# SH3_-_24V_BUCK-BOOST_CONVERTER.net
KiCad netlist of a schematic drawn in Altium Designer
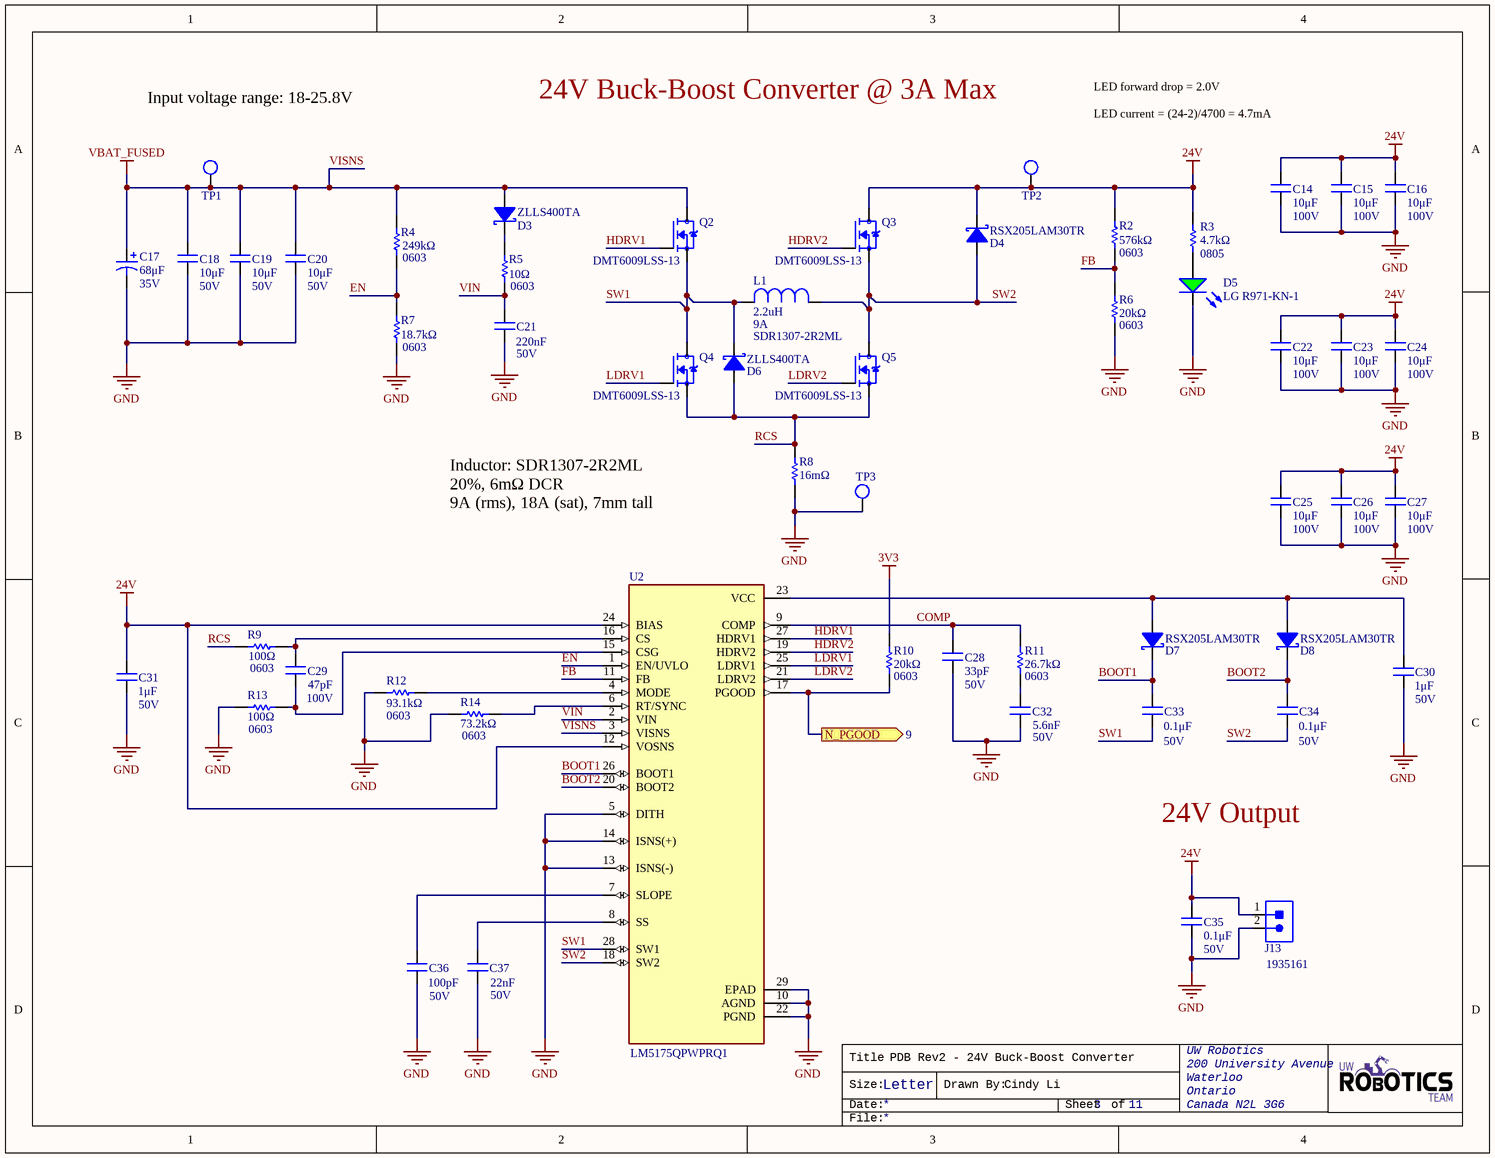
[diagram p0: SH3 - 24V BUCK-BOOST CONVERTER.SchDoc]

(export (version "E")
  (design (tool "Eeschema 10.0.6"))
  (components
    (comp (ref "C14")
      (value "10μF")
      (footprint "CAP1210")
      (description "CAP CER 10uF 100V X7S 10% 1210")
      (fields
        (field (name "TOLERANCE") "10%")
        (field (name "VOLTAGE RATING") "100V")
        (field (name "Comment") "CAP_10uF_100V_1210")
      )
      (libsource (lib "UWRT_Schematic_Library_2020") (part "CAP_10uF_100V_1210"))
    )
    (comp (ref "C15")
      (value "10μF")
      (footprint "CAP1210")
      (description "CAP CER 10uF 100V X7S 10% 1210")
      (fields
        (field (name "TOLERANCE") "10%")
        (field (name "VOLTAGE RATING") "100V")
        (field (name "Comment") "CAP_10uF_100V_1210")
      )
      (libsource (lib "UWRT_Schematic_Library_2020") (part "CAP_10uF_100V_1210"))
    )
    (comp (ref "C16")
      (value "10μF")
      (footprint "CAP1210")
      (description "CAP CER 10uF 100V X7S 10% 1210")
      (fields
        (field (name "TOLERANCE") "10%")
        (field (name "VOLTAGE RATING") "100V")
        (field (name "Comment") "CAP_10uF_100V_1210")
      )
      (libsource (lib "UWRT_Schematic_Library_2020") (part "CAP_10uF_100V_1210"))
    )
    (comp (ref "C17")
      (value "68μF")
      (footprint "RADIAL_NICHION_1V")
      (description "CAP ALUM 68UF 20% 35V SMD")
      (fields
        (field (name "TOLERANCE") "20%")
        (field (name "VOLTAGE RATING") "35V")
        (field (name "Comment") "CAP_68uF_35V_ALUM")
      )
      (libsource (lib "UWRT_Schematic_Library_2020") (part "CAP_68uF_35V_ALUM"))
    )
    (comp (ref "C18")
      (value "10μF")
      (footprint "CAP1210")
      (description "CAP CER 10UF 50V X7R 1210")
      (fields
        (field (name "TOLERANCE") "20%")
        (field (name "VOLTAGE RATING") "50V")
        (field (name "Comment") "CAP_10uF_50V_1210_TDK")
      )
      (libsource (lib "UWRT_Schematic_Library_2020") (part "CAP_10uF_50V_1210_TDK"))
    )
    (comp (ref "C19")
      (value "10μF")
      (footprint "CAP1210")
      (description "CAP CER 10UF 50V X7R 1210")
      (fields
        (field (name "TOLERANCE") "20%")
        (field (name "VOLTAGE RATING") "50V")
        (field (name "Comment") "CAP_10uF_50V_1210_TDK")
      )
      (libsource (lib "UWRT_Schematic_Library_2020") (part "CAP_10uF_50V_1210_TDK"))
    )
    (comp (ref "C20")
      (value "10μF")
      (footprint "CAP1210")
      (description "CAP CER 10UF 50V X7R 1210")
      (fields
        (field (name "TOLERANCE") "20%")
        (field (name "VOLTAGE RATING") "50V")
        (field (name "Comment") "CAP_10uF_50V_1210_TDK")
      )
      (libsource (lib "UWRT_Schematic_Library_2020") (part "CAP_10uF_50V_1210_TDK"))
    )
    (comp (ref "C21")
      (value "220nF")
      (footprint "CAP0603")
      (description "CAP CER 0.22UF 50V X7R 0603")
      (fields (field (name "VOLTAGE RATING") "50V") (field (name "Comment") "CAP_0.22uF_50V_0603"))
      (libsource (lib "UWRT_Schematic_Library_2020") (part "CAP_0.22uF_50V_0603"))
    )
    (comp (ref "C22")
      (value "10μF")
      (footprint "CAP1210")
      (description "CAP CER 10uF 100V X7S 10% 1210")
      (fields
        (field (name "TOLERANCE") "10%")
        (field (name "VOLTAGE RATING") "100V")
        (field (name "Comment") "CAP_10uF_100V_1210")
      )
      (libsource (lib "UWRT_Schematic_Library_2020") (part "CAP_10uF_100V_1210"))
    )
    (comp (ref "C23")
      (value "10μF")
      (footprint "CAP1210")
      (description "CAP CER 10uF 100V X7S 10% 1210")
      (fields
        (field (name "TOLERANCE") "10%")
        (field (name "VOLTAGE RATING") "100V")
        (field (name "Comment") "CAP_10uF_100V_1210")
      )
      (libsource (lib "UWRT_Schematic_Library_2020") (part "CAP_10uF_100V_1210"))
    )
    (comp (ref "C24")
      (value "10μF")
      (footprint "CAP1210")
      (description "CAP CER 10uF 100V X7S 10% 1210")
      (fields
        (field (name "TOLERANCE") "10%")
        (field (name "VOLTAGE RATING") "100V")
        (field (name "Comment") "CAP_10uF_100V_1210")
      )
      (libsource (lib "UWRT_Schematic_Library_2020") (part "CAP_10uF_100V_1210"))
    )
    (comp (ref "C25")
      (value "10μF")
      (footprint "CAP1210")
      (description "CAP CER 10uF 100V X7S 10% 1210")
      (fields
        (field (name "TOLERANCE") "10%")
        (field (name "VOLTAGE RATING") "100V")
        (field (name "Comment") "CAP_10uF_100V_1210")
      )
      (libsource (lib "UWRT_Schematic_Library_2020") (part "CAP_10uF_100V_1210"))
    )
    (comp (ref "C26")
      (value "10μF")
      (footprint "CAP1210")
      (description "CAP CER 10uF 100V X7S 10% 1210")
      (fields
        (field (name "TOLERANCE") "10%")
        (field (name "VOLTAGE RATING") "100V")
        (field (name "Comment") "CAP_10uF_100V_1210")
      )
      (libsource (lib "UWRT_Schematic_Library_2020") (part "CAP_10uF_100V_1210"))
    )
    (comp (ref "C27")
      (value "10μF")
      (footprint "CAP1210")
      (description "CAP CER 10uF 100V X7S 10% 1210")
      (fields
        (field (name "TOLERANCE") "10%")
        (field (name "VOLTAGE RATING") "100V")
        (field (name "Comment") "CAP_10uF_100V_1210")
      )
      (libsource (lib "UWRT_Schematic_Library_2020") (part "CAP_10uF_100V_1210"))
    )
    (comp (ref "C28")
      (value "33pF")
      (footprint "CAP2012")
      (description "CAP CER 33PF 50V C0G/NP0 0805")
      (fields
        (field (name "TOLERANCE") "5%")
        (field (name "VOLTAGE RATING") "50V")
        (field (name "Comment") "CAP_33pF_50V_0805")
      )
      (libsource (lib "UWRT_Schematic_Library_2020") (part "CAP_33pF_50V_0805"))
    )
    (comp (ref "C29")
      (value "47pF")
      (footprint "CAP0603")
      (description "CAP CER 47PF 100V C0G/NP0 0603")
      (fields (field (name "VOLTAGE RATING") "100V") (field (name "Comment") "CAP_47pF_100V_0603"))
      (libsource (lib "UWRT_Schematic_Library_2020") (part "CAP_47pF_100V_0603"))
    )
    (comp (ref "C30")
      (value "1μF")
      (footprint "CAP0603")
      (description "CAP CER 1UF 50V X6S 0603")
      (fields (field (name "VOLTAGE RATING") "50V") (field (name "Comment") "CAP_1uF_50V_0603"))
      (libsource (lib "UWRT_Schematic_Library_2020") (part "CAP_1uF_50V_0603"))
    )
    (comp (ref "C31")
      (value "1μF")
      (footprint "CAP0603")
      (description "CAP CER 1UF 50V X6S 0603")
      (fields (field (name "VOLTAGE RATING") "50V") (field (name "Comment") "CAP_1uF_50V_0603"))
      (libsource (lib "UWRT_Schematic_Library_2020") (part "CAP_1uF_50V_0603"))
    )
    (comp (ref "C32")
      (value "5600pF")
      (footprint "CAP2012")
      (description "CAP CER 5600PF 50V C0G 0805")
      (fields
        (field (name "TOLERANCE") "5%")
        (field (name "CAPACITANCE") "5.6nF")
        (field (name "VOLTAGE RATING") "50V")
      )
      (libsource (lib "UWRT_Schematic_Library_2020") (part "CAP_5600pF_50V_0805"))
    )
    (comp (ref "C33")
      (value "0.1μF")
      (footprint "CAP2012")
      (description "CAP CER 0.1UF 50V X7R 0805")
      (fields (field (name "TOLERANCE") "10%") (field (name "VOLTAGE RATING") "50V"))
      (libsource (lib "UWRT_Schematic_Library_2020") (part "CAP_0.1uF_50V_0805"))
    )
    (comp (ref "C34")
      (value "0.1μF")
      (footprint "CAP2012")
      (description "CAP CER 0.1UF 50V X7R 0805")
      (fields (field (name "TOLERANCE") "10%") (field (name "VOLTAGE RATING") "50V"))
      (libsource (lib "UWRT_Schematic_Library_2020") (part "CAP_0.1uF_50V_0805"))
    )
    (comp (ref "C35")
      (value "0.1μF")
      (footprint "CAP2012")
      (description "CAP CER 0.1UF 50V X7R 0805")
      (fields (field (name "TOLERANCE") "10%") (field (name "VOLTAGE RATING") "50V"))
      (libsource (lib "UWRT_Schematic_Library_2020") (part "CAP_0.1uF_50V_0805"))
    )
    (comp (ref "C36")
      (value "100pF")
      (footprint "CAP0603")
      (description "CAP CER 100PF 50V C0G/NP0 0603")
      (fields (field (name "VOLTAGE RATING") "50V") (field (name "Comment") "CAP_100pF_0603"))
      (libsource (lib "UWRT_Schematic_Library_2020") (part "CAP_100pF_0603"))
    )
    (comp (ref "C37")
      (value "22nF")
      (footprint "CAP2012")
      (description "CAP CER 0.022UF 50V C0G 0805")
      (fields
        (field (name "TOLERANCE") "5%")
        (field (name "VOLTAGE RATING") "50V")
        (field (name "Comment") "0.022μF")
      )
      (libsource (lib "UWRT_Schematic_Library_2020") (part "CAP_0.022uF_50V_0805"))
    )
    (comp (ref "D3")
      (value "DIO_SCHOTTKY_40V_520mA")
      (footprint "SOD-323")
      (description "DIODE SCHOTTKY 40V 520MA SOD323")
      (fields (field (name "MANUFACTURER PART NUMBER 1") "ZLLS400TA"))
      (libsource (lib "UWRT_Schematic_Library_2020") (part "DIO_SCHOTTKY_40V_520mA"))
    )
    (comp (ref "D4")
      (value "DIO_SCHOTTKY_30V_2A")
      (footprint "SOD-128")
      (description "DIODE SCHOTTKY 30V 2A PMDTM")
      (fields (field (name "MANUFACTURER PART NUMBER 1") "RSX205LAM30TR"))
      (libsource (lib "UWRT_Schematic_Library_2020") (part "DIO_SCHOTTKY_30V_2A"))
    )
    (comp (ref "D5")
      (value "LG R971-KN-1")
      (footprint "LED_0805_GREEN")
      (description "LED GREEN DIFFUSED 0805 SMD")
      (libsource (lib "UWRT_Schematic_Library_2020") (part "DIO_LED_G"))
    )
    (comp (ref "D6")
      (value "DIO_SCHOTTKY_40V_520mA")
      (footprint "SOD-323")
      (description "DIODE SCHOTTKY 40V 520MA SOD323")
      (fields (field (name "MANUFACTURER PART NUMBER 1") "ZLLS400TA"))
      (libsource (lib "UWRT_Schematic_Library_2020") (part "DIO_SCHOTTKY_40V_520mA"))
    )
    (comp (ref "D7")
      (value "DIO_SCHOTTKY_30V_2A")
      (footprint "SOD-128")
      (description "DIODE SCHOTTKY 30V 2A PMDTM")
      (fields (field (name "MANUFACTURER PART NUMBER 1") "RSX205LAM30TR"))
      (libsource (lib "UWRT_Schematic_Library_2020") (part "DIO_SCHOTTKY_30V_2A"))
    )
    (comp (ref "D8")
      (value "DIO_SCHOTTKY_30V_2A")
      (footprint "SOD-128")
      (description "DIODE SCHOTTKY 30V 2A PMDTM")
      (fields (field (name "MANUFACTURER PART NUMBER 1") "RSX205LAM30TR"))
      (libsource (lib "UWRT_Schematic_Library_2020") (part "DIO_SCHOTTKY_30V_2A"))
    )
    (comp (ref "J13")
      (value "1935161")
      (footprint "1935161")
      (description "TERM BLK 2POS SIDE ENTRY 5MM")
      (fields (field (name "VOLTAGE") "300V") (field (name "MANUFACTURER PART NUMBER 1") "1935161"))
      (libsource (lib "UWRT_Schematic_Library_2020") (part "CON_2M_TERM"))
    )
    (comp (ref "L1")
      (value "IND_2.2uH_9A")
      (footprint "IND_BOURNS_SDR1307")
      (description "FIXED IND 2.2UH 9A 6 MOHM SMD")
      (fields
        (field (name "TOLERANCE") "20%")
        (field (name "CURRENT RATING") "9A")
        (field (name "MANUFACTURER PART NUMBER 1") "SDR1307-2R2ML")
        (field (name "INDUCTANCE") "2.2uH")
      )
      (libsource (lib "UWRT_Schematic_Library_2020") (part "IND_2.2uH_9A"))
    )
    (comp (ref "Q2")
      (value "NMOS_60V_10.8A")
      (footprint "TRANS_DMP2002UPS-13")
      (description "MOSFET BVDSS: 41V 60V,SO-8,T&R,2")
      (fields (field (name "MANUFACTURER PART NUMBER 1") "DMT6009LSS-13"))
      (libsource (lib "UWRT_Schematic_Library_2020") (part "NMOS_60V_10.8A"))
    )
    (comp (ref "Q3")
      (value "NMOS_60V_10.8A")
      (footprint "TRANS_DMP2002UPS-13")
      (description "MOSFET BVDSS: 41V 60V,SO-8,T&R,2")
      (fields (field (name "MANUFACTURER PART NUMBER 1") "DMT6009LSS-13"))
      (libsource (lib "UWRT_Schematic_Library_2020") (part "NMOS_60V_10.8A"))
    )
    (comp (ref "Q4")
      (value "NMOS_60V_10.8A")
      (footprint "TRANS_DMP2002UPS-13")
      (description "MOSFET BVDSS: 41V 60V,SO-8,T&R,2")
      (fields (field (name "MANUFACTURER PART NUMBER 1") "DMT6009LSS-13"))
      (libsource (lib "UWRT_Schematic_Library_2020") (part "NMOS_60V_10.8A"))
    )
    (comp (ref "Q5")
      (value "NMOS_60V_10.8A")
      (footprint "TRANS_DMP2002UPS-13")
      (description "MOSFET BVDSS: 41V 60V,SO-8,T&R,2")
      (fields (field (name "MANUFACTURER PART NUMBER 1") "DMT6009LSS-13"))
      (libsource (lib "UWRT_Schematic_Library_2020") (part "NMOS_60V_10.8A"))
    )
    (comp (ref "R2")
      (value "576kΩ")
      (footprint "RESC0603(1608)_N")
      (description "RES 576K OHM 1% 1/10W 0603")
      (fields
        (field (name "CASE CODE (IMPERIAL)") "0603")
        (field (name "TOLERANCE") "1%")
        (field (name "Comment") "RES_576kΩ_0603")
      )
      (libsource (lib "UWRT_Schematic_Library_2020") (part "RES_576kΩ_0603_1%"))
    )
    (comp (ref "R3")
      (value "4.7kΩ")
      (footprint "RESC2012X60N")
      (description "RES 4.7K OHM 5% 1/8W 0805")
      (fields
        (field (name "TOLERANCE") "5%")
        (field (name "CASE CODE (IMPERIAL)") "0805")
        (field (name "Comment") "RES_4.7kΩ_0805")
      )
      (libsource (lib "UWRT_Schematic_Library_2020") (part "RES_4.7kΩ_0805_5%"))
    )
    (comp (ref "R4")
      (value "249kΩ")
      (footprint "RESC0603(1608)_N")
      (description "RES 249K OHM 1% 1/10W 0603")
      (fields
        (field (name "CASE CODE (IMPERIAL)") "0603")
        (field (name "POWER") "0.1W")
        (field (name "TOLERANCE") "1%")
      )
      (libsource (lib "UWRT_Schematic_Library_2020") (part "RES_249kΩ_0603_1%"))
    )
    (comp (ref "R5")
      (value "10Ω")
      (footprint "RESC0603(1608)_N")
      (description "RES 10 OHM 1% 1/10W 0603")
      (fields
        (field (name "CASE CODE (IMPERIAL)") "0603")
        (field (name "TOLERANCE") "1%")
        (field (name "Comment") "RES_10Ω_0603")
      )
      (libsource (lib "UWRT_Schematic_Library_2020") (part "RES_10Ω_0603_1%"))
    )
    (comp (ref "R6")
      (value "20kΩ")
      (footprint "RESC0603(1608)_N")
      (description "RES 20K OHM 1% 1/10W 0603")
      (fields
        (field (name "CASE CODE (IMPERIAL)") "0603")
        (field (name "TOLERANCE") "1%")
        (field (name "Comment") "RES_20kΩ_0603")
      )
      (libsource (lib "UWRT_Schematic_Library_2020") (part "RES_20kΩ_0603_1%"))
    )
    (comp (ref "R7")
      (value "18.7kΩ")
      (footprint "RESC0603(1608)_N")
      (description "RES 18.7K OHM 1% 1/10W 0603")
      (fields
        (field (name "CASE CODE (IMPERIAL)") "0603")
        (field (name "TOLERANCE") "1%")
        (field (name "Comment") "RES_18.7kΩ_0603_1%")
      )
      (libsource (lib "UWRT_Schematic_Library_2020") (part "RES_18.7kΩ_0603_1%"))
    )
    (comp (ref "R8")
      (value "16mΩ")
      (footprint "RESC1632X60N")
      (description "RES 0.016 OHM 1W 1206 WIDE")
      (fields (field (name "TOLERANCE") "1%") (field (name "Comment") "RES_16mΩ_1206"))
      (libsource (lib "UWRT_Schematic_Library_2020") (part "RES_16mΩ_1206_1%"))
    )
    (comp (ref "R9")
      (value "100Ω")
      (footprint "RESC0603(1608)_N")
      (description "RES 100 OHM 1% 1/10W 0603")
      (fields
        (field (name "CASE CODE (IMPERIAL)") "0603")
        (field (name "TOLERANCE") "1%")
        (field (name "Comment") "RES_100Ω_0603")
      )
      (libsource (lib "UWRT_Schematic_Library_2020") (part "RES_100Ω_0603_1%"))
    )
    (comp (ref "R10")
      (value "20kΩ")
      (footprint "RESC0603(1608)_N")
      (description "RES 20K OHM 1% 1/10W 0603")
      (fields
        (field (name "CASE CODE (IMPERIAL)") "0603")
        (field (name "TOLERANCE") "1%")
        (field (name "Comment") "RES_20kΩ_0603")
      )
      (libsource (lib "UWRT_Schematic_Library_2020") (part "RES_20kΩ_0603_1%"))
    )
    (comp (ref "R11")
      (value "26.7kΩ")
      (footprint "RESC0603(1608)_N")
      (description "RES 26.7K OHM 1% 1/10W 0603")
      (fields
        (field (name "CASE CODE (IMPERIAL)") "0603")
        (field (name "POWER") "0.1W")
        (field (name "TOLERANCE") "1%")
      )
      (libsource (lib "UWRT_Schematic_Library_2020") (part "RES_26.7kΩ_0603_1%"))
    )
    (comp (ref "R12")
      (value "93.1kΩ")
      (footprint "RESC0603(1608)_N")
      (description "RES 93.1K OHM 1% 1/10W 0603")
      (fields
        (field (name "TOLERANCE") "1%")
        (field (name "CASE CODE (IMPERIAL)") "0603")
        (field (name "Comment") "RES_93.1kΩ_0603")
      )
      (libsource (lib "UWRT_Schematic_Library_2020") (part "RES_93.1kΩ_0603_1%"))
    )
    (comp (ref "R13")
      (value "100Ω")
      (footprint "RESC0603(1608)_N")
      (description "RES 100 OHM 1% 1/10W 0603")
      (fields
        (field (name "CASE CODE (IMPERIAL)") "0603")
        (field (name "TOLERANCE") "1%")
        (field (name "Comment") "RES_100Ω_0603")
      )
      (libsource (lib "UWRT_Schematic_Library_2020") (part "RES_100Ω_0603_1%"))
    )
    (comp (ref "R14")
      (value "73.2kΩ")
      (footprint "RESC0603(1608)_N")
      (description "RES 73.2K OHM 1% 1/16W 0603")
      (fields
        (field (name "CASE CODE (IMPERIAL)") "0603")
        (field (name "TOLERANCE") "1%")
        (field (name "Comment") "RES_73.2kΩ_0603")
      )
      (libsource (lib "UWRT_Schematic_Library_2020") (part "RES_73.2kΩ_0603_1%"))
    )
    (comp (ref "TP1")
      (value "TESTPOINT_LOOP")
      (footprint "TESTPOINT_LOOP")
      (description "PC TEST POINT MINIATURE WHITE")
      (libsource (lib "UWRT_Schematic_Library_2020") (part "TESTPOINT_LOOP"))
    )
    (comp (ref "TP2")
      (value "TESTPOINT_LOOP")
      (footprint "TESTPOINT_LOOP")
      (description "PC TEST POINT MINIATURE WHITE")
      (libsource (lib "UWRT_Schematic_Library_2020") (part "TESTPOINT_LOOP"))
    )
    (comp (ref "TP3")
      (value "TESTPOINT_LOOP")
      (footprint "TESTPOINT_LOOP")
      (description "PC TEST POINT MINIATURE WHITE")
      (libsource (lib "UWRT_Schematic_Library_2020") (part "TESTPOINT_LOOP"))
    )
    (comp (ref "U2")
      (value "LM5175PWPR")
      (footprint "IC_TPS61196PWPRQ1")
      (description "IC REG CTRLR BUCK-BOOST 28HTSSOP")
      (fields (field (name "MANUFACTURER PART NUMBER 1") "LM5175QPWPRQ1"))
      (libsource (lib "UWRT_Schematic_Library_2020") (part "LM5175PWPR"))
    )
  )
  (nets
    (net (code "1") (name "/BOOT1") (class "Default")
      (node (ref "C33") (pin "2") (pinfunction "2_2") (pintype "passive"))
      (node (ref "D7") (pin "2") (pinfunction "Cathode_2") (pintype "passive"))
      (node (ref "U2") (pin "26") (pinfunction "BOOT1_26") (pintype "bidirectional"))
    )
    (net (code "2") (name "/BOOT2") (class "Default")
      (node (ref "C34") (pin "2") (pinfunction "2_2") (pintype "passive"))
      (node (ref "D8") (pin "2") (pinfunction "Cathode_2") (pintype "passive"))
      (node (ref "U2") (pin "20") (pinfunction "BOOT2_20") (pintype "bidirectional"))
    )
    (net (code "3") (name "/COMP") (class "Default")
      (node (ref "C28") (pin "2") (pinfunction "2_2") (pintype "passive"))
      (node (ref "R11") (pin "2") (pinfunction "2_2") (pintype "passive"))
      (node (ref "U2") (pin "9") (pinfunction "COMP_9") (pintype "output"))
    )
    (net (code "4") (name "/EN") (class "Default")
      (node (ref "R4") (pin "1") (pinfunction "1_1") (pintype "passive"))
      (node (ref "R7") (pin "2") (pinfunction "2_2") (pintype "passive"))
      (node (ref "U2") (pin "1") (pinfunction "EN/UVLO_1") (pintype "input"))
    )
    (net (code "5") (name "/FB") (class "Default")
      (node (ref "R2") (pin "1") (pinfunction "1_1") (pintype "passive"))
      (node (ref "R6") (pin "2") (pinfunction "2_2") (pintype "passive"))
      (node (ref "U2") (pin "11") (pinfunction "FB_11") (pintype "input"))
    )
    (net (code "6") (name "/HDRV1") (class "Default")
      (node (ref "Q2") (pin "3") (pinfunction "G_3") (pintype "passive"))
      (node (ref "U2") (pin "27") (pinfunction "HDRV1_27") (pintype "output"))
    )
    (net (code "7") (name "/HDRV2") (class "Default")
      (node (ref "Q3") (pin "3") (pinfunction "G_3") (pintype "passive"))
      (node (ref "U2") (pin "19") (pinfunction "HDRV2_19") (pintype "output"))
    )
    (net (code "8") (name "/LDRV1") (class "Default")
      (node (ref "Q4") (pin "3") (pinfunction "G_3") (pintype "passive"))
      (node (ref "U2") (pin "25") (pinfunction "LDRV1_25") (pintype "output"))
    )
    (net (code "9") (name "/LDRV2") (class "Default")
      (node (ref "Q5") (pin "3") (pinfunction "G_3") (pintype "passive"))
      (node (ref "U2") (pin "21") (pinfunction "LDRV2_21") (pintype "output"))
    )
    (net (code "10") (name "/N_PGOOD") (class "Default")
      (node (ref "R10") (pin "1") (pinfunction "1_1") (pintype "passive"))
      (node (ref "U2") (pin "17") (pinfunction "PGOOD_17") (pintype "output"))
    )
    (net (code "11") (name "/RCS") (class "Default")
      (node (ref "D6") (pin "1") (pinfunction "Anode_1") (pintype "passive"))
      (node (ref "Q4") (pin "2") (pinfunction "S_2") (pintype "passive"))
      (node (ref "Q5") (pin "2") (pinfunction "S_2") (pintype "passive"))
      (node (ref "R8") (pin "2") (pinfunction "2_2") (pintype "passive"))
      (node (ref "R9") (pin "1") (pinfunction "1_1") (pintype "passive"))
    )
    (net (code "12") (name "/SW1") (class "Default")
      (node (ref "C33") (pin "1") (pinfunction "1_1") (pintype "passive"))
      (node (ref "D6") (pin "2") (pinfunction "Cathode_2") (pintype "passive"))
      (node (ref "L1") (pin "2") (pinfunction "2_2") (pintype "passive"))
      (node (ref "Q2") (pin "2") (pinfunction "S_2") (pintype "passive"))
      (node (ref "Q4") (pin "1") (pinfunction "D_1") (pintype "passive"))
      (node (ref "U2") (pin "28") (pinfunction "SW1_28") (pintype "bidirectional"))
    )
    (net (code "13") (name "/SW2") (class "Default")
      (node (ref "C34") (pin "1") (pinfunction "1_1") (pintype "passive"))
      (node (ref "D4") (pin "1") (pinfunction "Anode_1") (pintype "passive"))
      (node (ref "L1") (pin "1") (pinfunction "1_1") (pintype "passive"))
      (node (ref "Q3") (pin "2") (pinfunction "S_2") (pintype "passive"))
      (node (ref "Q5") (pin "1") (pinfunction "D_1") (pintype "passive"))
      (node (ref "U2") (pin "18") (pinfunction "SW2_18") (pintype "bidirectional"))
    )
    (net (code "14") (name "/VIN") (class "Default")
      (node (ref "C21") (pin "2") (pinfunction "2_2") (pintype "passive"))
      (node (ref "R5") (pin "1") (pinfunction "1_1") (pintype "passive"))
      (node (ref "U2") (pin "2") (pinfunction "VIN_2") (pintype "input"))
    )
    (net (code "15") (name "3V3") (class "Default")
      (node (ref "R10") (pin "2") (pinfunction "2_2") (pintype "passive"))
    )
    (net (code "16") (name "24V") (class "Default")
      (node (ref "C14") (pin "1") (pinfunction "1_1") (pintype "passive"))
      (node (ref "C15") (pin "1") (pinfunction "1_1") (pintype "passive"))
      (node (ref "C16") (pin "2") (pinfunction "2_2") (pintype "passive"))
      (node (ref "C22") (pin "1") (pinfunction "1_1") (pintype "passive"))
      (node (ref "C23") (pin "1") (pinfunction "1_1") (pintype "passive"))
      (node (ref "C24") (pin "2") (pinfunction "2_2") (pintype "passive"))
      (node (ref "C25") (pin "1") (pinfunction "1_1") (pintype "passive"))
      (node (ref "C26") (pin "1") (pinfunction "1_1") (pintype "passive"))
      (node (ref "C27") (pin "2") (pinfunction "2_2") (pintype "passive"))
      (node (ref "C31") (pin "2") (pinfunction "2_2") (pintype "passive"))
      (node (ref "C35") (pin "2") (pinfunction "2_2") (pintype "passive"))
      (node (ref "D4") (pin "2") (pinfunction "Cathode_2") (pintype "passive"))
      (node (ref "J13") (pin "1") (pinfunction "1_1") (pintype "passive"))
      (node (ref "Q3") (pin "1") (pinfunction "D_1") (pintype "passive"))
      (node (ref "R2") (pin "2") (pinfunction "2_2") (pintype "passive"))
      (node (ref "R3") (pin "2") (pinfunction "2_2") (pintype "passive"))
      (node (ref "TP2") (pin "1") (pintype "passive"))
      (node (ref "U2") (pin "12") (pinfunction "VOSNS_12") (pintype "input"))
      (node (ref "U2") (pin "24") (pinfunction "BIAS_24") (pintype "input"))
    )
    (net (code "17") (name "GND") (class "Default")
      (node (ref "C14") (pin "2") (pinfunction "2_2") (pintype "passive"))
      (node (ref "C15") (pin "2") (pinfunction "2_2") (pintype "passive"))
      (node (ref "C16") (pin "1") (pinfunction "1_1") (pintype "passive"))
      (node (ref "C17") (pin "2") (pinfunction "2_2") (pintype "passive"))
      (node (ref "C18") (pin "1") (pinfunction "1_1") (pintype "passive"))
      (node (ref "C19") (pin "1") (pinfunction "1_1") (pintype "passive"))
      (node (ref "C20") (pin "1") (pinfunction "1_1") (pintype "passive"))
      (node (ref "C21") (pin "1") (pinfunction "1_1") (pintype "passive"))
      (node (ref "C22") (pin "2") (pinfunction "2_2") (pintype "passive"))
      (node (ref "C23") (pin "2") (pinfunction "2_2") (pintype "passive"))
      (node (ref "C24") (pin "1") (pinfunction "1_1") (pintype "passive"))
      (node (ref "C25") (pin "2") (pinfunction "2_2") (pintype "passive"))
      (node (ref "C26") (pin "2") (pinfunction "2_2") (pintype "passive"))
      (node (ref "C27") (pin "1") (pinfunction "1_1") (pintype "passive"))
      (node (ref "C28") (pin "1") (pinfunction "1_1") (pintype "passive"))
      (node (ref "C30") (pin "1") (pinfunction "1_1") (pintype "passive"))
      (node (ref "C31") (pin "1") (pinfunction "1_1") (pintype "passive"))
      (node (ref "C32") (pin "1") (pinfunction "1_1") (pintype "passive"))
      (node (ref "C35") (pin "1") (pinfunction "1_1") (pintype "passive"))
      (node (ref "C36") (pin "1") (pinfunction "1_1") (pintype "passive"))
      (node (ref "C37") (pin "1") (pinfunction "1_1") (pintype "passive"))
      (node (ref "D5") (pin "2") (pinfunction "K_2") (pintype "passive"))
      (node (ref "J13") (pin "2") (pinfunction "2_2") (pintype "passive"))
      (node (ref "R12") (pin "1") (pinfunction "1_1") (pintype "passive"))
      (node (ref "R13") (pin "1") (pinfunction "1_1") (pintype "passive"))
      (node (ref "R14") (pin "1") (pinfunction "1_1") (pintype "passive"))
      (node (ref "R6") (pin "1") (pinfunction "1_1") (pintype "passive"))
      (node (ref "R7") (pin "1") (pinfunction "1_1") (pintype "passive"))
      (node (ref "R8") (pin "1") (pinfunction "1_1") (pintype "passive"))
      (node (ref "TP3") (pin "1") (pintype "passive"))
      (node (ref "U2") (pin "10") (pinfunction "AGND_10") (pintype "power_in"))
      (node (ref "U2") (pin "13") (pinfunction "ISNS(-)_13") (pintype "bidirectional"))
      (node (ref "U2") (pin "14") (pinfunction "ISNS(+)_14") (pintype "bidirectional"))
      (node (ref "U2") (pin "22") (pinfunction "PGND_22") (pintype "power_in"))
      (node (ref "U2") (pin "29") (pinfunction "EPAD_29") (pintype "power_in"))
      (node (ref "U2") (pin "5") (pinfunction "DITH_5") (pintype "bidirectional"))
    )
    (net (code "18") (name "Net-(C32-Pad2)") (class "Default")
      (node (ref "C32") (pin "2") (pinfunction "2_2") (pintype "passive"))
      (node (ref "R11") (pin "1") (pinfunction "1_1") (pintype "passive"))
    )
    (net (code "19") (name "Net-(D3-Cathode)") (class "Default")
      (node (ref "D3") (pin "2") (pinfunction "Cathode_2") (pintype "passive"))
      (node (ref "R5") (pin "2") (pinfunction "2_2") (pintype "passive"))
    )
    (net (code "20") (name "Net-(D5-A)") (class "Default")
      (node (ref "D5") (pin "1") (pinfunction "A_1") (pintype "passive"))
      (node (ref "R3") (pin "1") (pinfunction "1_1") (pintype "passive"))
    )
    (net (code "21") (name "Net-(D7-Anode)") (class "Default")
      (node (ref "C30") (pin "2") (pinfunction "2_2") (pintype "passive"))
      (node (ref "D7") (pin "1") (pinfunction "Anode_1") (pintype "passive"))
      (node (ref "D8") (pin "1") (pinfunction "Anode_1") (pintype "passive"))
      (node (ref "U2") (pin "23") (pinfunction "VCC_23") (pintype "power_in"))
    )
    (net (code "22") (name "Net-(U2-CS)") (class "Default")
      (node (ref "C29") (pin "1") (pinfunction "1_1") (pintype "passive"))
      (node (ref "R9") (pin "2") (pinfunction "2_2") (pintype "passive"))
      (node (ref "U2") (pin "16") (pinfunction "CS_16") (pintype "input"))
    )
    (net (code "23") (name "Net-(U2-CSG)") (class "Default")
      (node (ref "C29") (pin "2") (pinfunction "2_2") (pintype "passive"))
      (node (ref "R13") (pin "2") (pinfunction "2_2") (pintype "passive"))
      (node (ref "U2") (pin "15") (pinfunction "CSG_15") (pintype "input"))
    )
    (net (code "24") (name "Net-(U2-MODE)") (class "Default")
      (node (ref "R12") (pin "2") (pinfunction "2_2") (pintype "passive"))
      (node (ref "U2") (pin "4") (pinfunction "MODE_4") (pintype "input"))
    )
    (net (code "25") (name "Net-(U2-RT{slash}SYNC)") (class "Default")
      (node (ref "R14") (pin "2") (pinfunction "2_2") (pintype "passive"))
      (node (ref "U2") (pin "6") (pinfunction "RT/SYNC_6") (pintype "input"))
    )
    (net (code "26") (name "Net-(U2-SLOPE)") (class "Default")
      (node (ref "C36") (pin "2") (pinfunction "2_2") (pintype "passive"))
      (node (ref "U2") (pin "7") (pinfunction "SLOPE_7") (pintype "bidirectional"))
    )
    (net (code "27") (name "Net-(U2-SS)") (class "Default")
      (node (ref "C37") (pin "2") (pinfunction "2_2") (pintype "passive"))
      (node (ref "U2") (pin "8") (pinfunction "SS_8") (pintype "bidirectional"))
    )
    (net (code "28") (name "VBAT_FUSED") (class "Default")
      (node (ref "C17") (pin "1") (pinfunction "1_1") (pintype "passive"))
      (node (ref "C18") (pin "2") (pinfunction "2_2") (pintype "passive"))
      (node (ref "C19") (pin "2") (pinfunction "2_2") (pintype "passive"))
      (node (ref "C20") (pin "2") (pinfunction "2_2") (pintype "passive"))
      (node (ref "D3") (pin "1") (pinfunction "Anode_1") (pintype "passive"))
      (node (ref "Q2") (pin "1") (pinfunction "D_1") (pintype "passive"))
      (node (ref "R4") (pin "2") (pinfunction "2_2") (pintype "passive"))
      (node (ref "TP1") (pin "1") (pintype "passive"))
      (node (ref "U2") (pin "3") (pinfunction "VISNS_3") (pintype "input"))
    )
  )
)
